# beer_machine_HAT.net
KiCad netlist of a schematic drawn in EAGLE
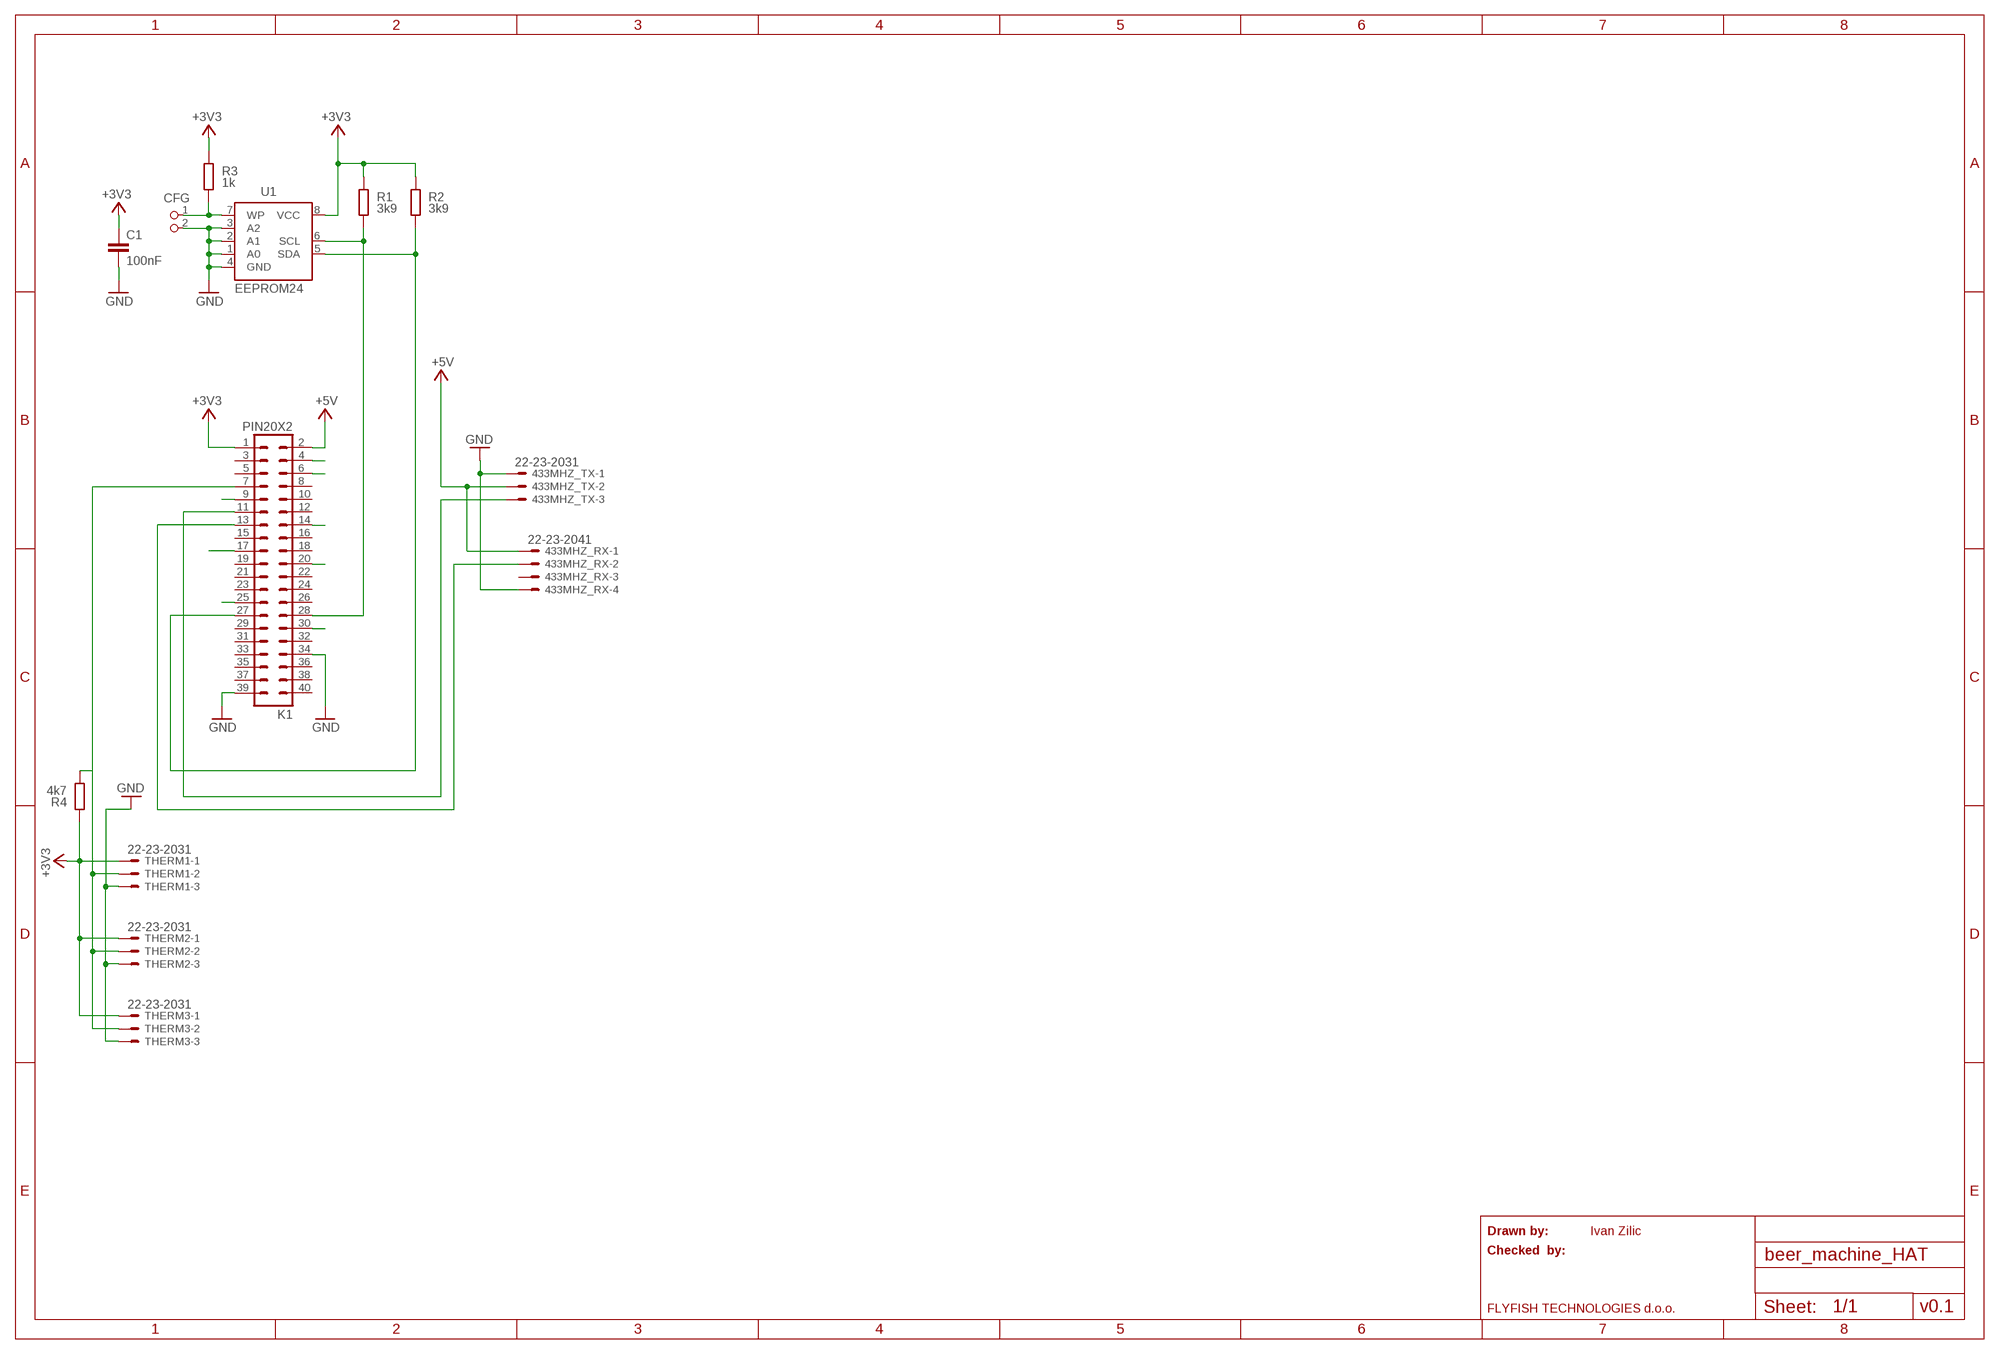
[diagram p0: schematic, sheet 1]

(export (version "E")
  (design (tool "Eeschema 10.0.6"))
  (components
    (comp (ref "433MHZ_RX")
      (value "22-23-2041")
      (footprint "eagle-import:22-23-2041")
      (fields (field (name "MF") "MOLEX"))
      (libsource (lib "eagle-import") (part "22-23-2041"))
    )
    (comp (ref "433MHZ_TX")
      (value "22-23-2031")
      (footprint "eagle-import:22-23-2031")
      (fields (field (name "MF") "MOLEX"))
      (libsource (lib "eagle-import") (part "22-23-2031"))
    )
    (comp (ref "C1")
      (value "100nF")
      (footprint "eagle-import:C0805K")
      (libsource (lib "eagle-import") (part "C-EUC0805K"))
    )
    (comp (ref "CFG")
      (value "PIN2_100")
      (footprint "eagle-import:PIN_W_2")
      (libsource (lib "eagle-import") (part "PIN2_100"))
    )
    (comp (ref "K1")
      (value "PIN20X2")
      (footprint "eagle-import:PIN_20X2")
      (libsource (lib "eagle-import") (part "PIN20X2"))
    )
    (comp (ref "R1")
      (value "3k9")
      (footprint "eagle-import:M0805")
      (fields (field (name "TOLERANCE") "5%"))
      (libsource (lib "eagle-import") (part "R-EU_M0805"))
    )
    (comp (ref "R2")
      (value "3k9")
      (footprint "eagle-import:M0805")
      (fields (field (name "TOLERANCE") "5%"))
      (libsource (lib "eagle-import") (part "R-EU_M0805"))
    )
    (comp (ref "R3")
      (value "1k")
      (footprint "eagle-import:M0805")
      (fields (field (name "TOLERANCE") "5%"))
      (libsource (lib "eagle-import") (part "R-EU_M0805"))
    )
    (comp (ref "R4")
      (value "4k7")
      (footprint "eagle-import:M0805")
      (fields (field (name "TOLERANCE") "5%"))
      (libsource (lib "eagle-import") (part "R-EU_M0805"))
    )
    (comp (ref "THERM1")
      (value "22-23-2031")
      (footprint "eagle-import:22-23-2031")
      (fields (field (name "MF") "MOLEX"))
      (libsource (lib "eagle-import") (part "22-23-2031"))
    )
    (comp (ref "THERM2")
      (value "22-23-2031")
      (footprint "eagle-import:22-23-2031")
      (fields (field (name "MF") "MOLEX"))
      (libsource (lib "eagle-import") (part "22-23-2031"))
    )
    (comp (ref "THERM3")
      (value "22-23-2031")
      (footprint "eagle-import:22-23-2031")
      (fields (field (name "MF") "MOLEX"))
      (libsource (lib "eagle-import") (part "22-23-2031"))
    )
    (comp (ref "U1")
      (value "EEPROM24")
      (footprint "eagle-import:SOIC8")
      (libsource (lib "eagle-import") (part "EEPROM24"))
    )
  )
  (nets
    (net (code "1") (name "+3V3") (class "Default")
      (node (ref "C1") (pin "1") (pinfunction "1_1") (pintype "passive"))
      (node (ref "K1") (pin "1") (pinfunction "1_1") (pintype "passive"))
      (node (ref "R1") (pin "2") (pinfunction "2_2") (pintype "passive"))
      (node (ref "R2") (pin "2") (pinfunction "2_2") (pintype "passive"))
      (node (ref "R3") (pin "2") (pinfunction "2_2") (pintype "passive"))
      (node (ref "R4") (pin "2") (pinfunction "2_2") (pintype "passive"))
      (node (ref "THERM1") (pin "1") (pinfunction "S_1") (pintype "passive"))
      (node (ref "THERM2") (pin "1") (pinfunction "S_1") (pintype "passive"))
      (node (ref "THERM3") (pin "1") (pinfunction "S_1") (pintype "passive"))
      (node (ref "U1") (pin "8") (pinfunction "VCC_8") (pintype "power_in"))
    )
    (net (code "2") (name "+5V") (class "Default")
      (node (ref "433MHZ_RX") (pin "1") (pinfunction "S_1") (pintype "passive"))
      (node (ref "433MHZ_TX") (pin "2") (pinfunction "S_2") (pintype "passive"))
      (node (ref "K1") (pin "2") (pinfunction "2_2") (pintype "passive"))
    )
    (net (code "3") (name "GND") (class "Default")
      (node (ref "433MHZ_RX") (pin "4") (pinfunction "S_4") (pintype "passive"))
      (node (ref "433MHZ_TX") (pin "1") (pinfunction "S_1") (pintype "passive"))
      (node (ref "C1") (pin "2") (pinfunction "2_2") (pintype "passive"))
      (node (ref "CFG") (pin "2") (pinfunction "2_2") (pintype "passive"))
      (node (ref "K1") (pin "34") (pinfunction "34_34") (pintype "passive"))
      (node (ref "K1") (pin "39") (pinfunction "39_39") (pintype "passive"))
      (node (ref "THERM1") (pin "3") (pinfunction "S_3") (pintype "passive"))
      (node (ref "THERM2") (pin "3") (pinfunction "S_3") (pintype "passive"))
      (node (ref "THERM3") (pin "3") (pinfunction "S_3") (pintype "passive"))
      (node (ref "U1") (pin "1") (pinfunction "A0_1") (pintype "input"))
      (node (ref "U1") (pin "2") (pinfunction "A1_2") (pintype "input"))
      (node (ref "U1") (pin "3") (pinfunction "A2_3") (pintype "input"))
      (node (ref "U1") (pin "4") (pinfunction "GND_4") (pintype "power_in"))
    )
    (net (code "4") (name "Net-(433MHZ_RXB-S)") (class "Default")
      (node (ref "433MHZ_RX") (pin "2") (pinfunction "S_2") (pintype "passive"))
      (node (ref "K1") (pin "13") (pinfunction "13_13") (pintype "passive"))
    )
    (net (code "5") (name "Net-(433MHZ_TXC-S)") (class "Default")
      (node (ref "433MHZ_TX") (pin "3") (pinfunction "S_3") (pintype "passive"))
      (node (ref "K1") (pin "11") (pinfunction "11_11") (pintype "passive"))
    )
    (net (code "6") (name "Net-(THERM1B-S)") (class "Default")
      (node (ref "K1") (pin "7") (pinfunction "7_7") (pintype "passive"))
      (node (ref "R4") (pin "1") (pinfunction "1_1") (pintype "passive"))
      (node (ref "THERM1") (pin "2") (pinfunction "S_2") (pintype "passive"))
      (node (ref "THERM2") (pin "2") (pinfunction "S_2") (pintype "passive"))
      (node (ref "THERM3") (pin "2") (pinfunction "S_2") (pintype "passive"))
    )
    (net (code "7") (name "Net-(U1-SCL)") (class "Default")
      (node (ref "K1") (pin "28") (pinfunction "28_28") (pintype "passive"))
      (node (ref "R1") (pin "1") (pinfunction "1_1") (pintype "passive"))
      (node (ref "U1") (pin "6") (pinfunction "SCL_6") (pintype "input"))
    )
    (net (code "8") (name "Net-(U1-SDA)") (class "Default")
      (node (ref "K1") (pin "27") (pinfunction "27_27") (pintype "passive"))
      (node (ref "R2") (pin "1") (pinfunction "1_1") (pintype "passive"))
      (node (ref "U1") (pin "5") (pinfunction "SDA_5") (pintype "bidirectional"))
    )
    (net (code "9") (name "Net-(U1-WP)") (class "Default")
      (node (ref "CFG") (pin "1") (pinfunction "1_1") (pintype "passive"))
      (node (ref "R3") (pin "1") (pinfunction "1_1") (pintype "passive"))
      (node (ref "U1") (pin "7") (pinfunction "WP_7") (pintype "input"))
    )
    (net (code "10") (name "unconnected-(433MHZ_RXC-S-Pad3)") (class "Default")
      (node (ref "433MHZ_RX") (pin "3") (pinfunction "S_3") (pintype "passive"))
    )
    (net (code "11") (name "unconnected-(K1-Pad3)") (class "Default")
      (node (ref "K1") (pin "3") (pinfunction "3_3") (pintype "passive"))
    )
    (net (code "12") (name "unconnected-(K1-Pad4)") (class "Default")
      (node (ref "K1") (pin "4") (pinfunction "4_4") (pintype "passive"))
    )
    (net (code "13") (name "unconnected-(K1-Pad5)") (class "Default")
      (node (ref "K1") (pin "5") (pinfunction "5_5") (pintype "passive"))
    )
    (net (code "14") (name "unconnected-(K1-Pad6)") (class "Default")
      (node (ref "K1") (pin "6") (pinfunction "6_6") (pintype "passive"))
    )
    (net (code "15") (name "unconnected-(K1-Pad8)") (class "Default")
      (node (ref "K1") (pin "8") (pinfunction "8_8") (pintype "passive"))
    )
    (net (code "16") (name "unconnected-(K1-Pad9)") (class "Default")
      (node (ref "K1") (pin "9") (pinfunction "9_9") (pintype "passive"))
    )
    (net (code "17") (name "unconnected-(K1-Pad10)") (class "Default")
      (node (ref "K1") (pin "10") (pinfunction "10_10") (pintype "passive"))
    )
    (net (code "18") (name "unconnected-(K1-Pad12)") (class "Default")
      (node (ref "K1") (pin "12") (pinfunction "12_12") (pintype "passive"))
    )
    (net (code "19") (name "unconnected-(K1-Pad14)") (class "Default")
      (node (ref "K1") (pin "14") (pinfunction "14_14") (pintype "passive"))
    )
    (net (code "20") (name "unconnected-(K1-Pad15)") (class "Default")
      (node (ref "K1") (pin "15") (pinfunction "15_15") (pintype "passive"))
    )
    (net (code "21") (name "unconnected-(K1-Pad16)") (class "Default")
      (node (ref "K1") (pin "16") (pinfunction "16_16") (pintype "passive"))
    )
    (net (code "22") (name "unconnected-(K1-Pad17)") (class "Default")
      (node (ref "K1") (pin "17") (pinfunction "17_17") (pintype "passive"))
    )
    (net (code "23") (name "unconnected-(K1-Pad18)") (class "Default")
      (node (ref "K1") (pin "18") (pinfunction "18_18") (pintype "passive"))
    )
    (net (code "24") (name "unconnected-(K1-Pad19)") (class "Default")
      (node (ref "K1") (pin "19") (pinfunction "19_19") (pintype "passive"))
    )
    (net (code "25") (name "unconnected-(K1-Pad20)") (class "Default")
      (node (ref "K1") (pin "20") (pinfunction "20_20") (pintype "passive"))
    )
    (net (code "26") (name "unconnected-(K1-Pad21)") (class "Default")
      (node (ref "K1") (pin "21") (pinfunction "21_21") (pintype "passive"))
    )
    (net (code "27") (name "unconnected-(K1-Pad22)") (class "Default")
      (node (ref "K1") (pin "22") (pinfunction "22_22") (pintype "passive"))
    )
    (net (code "28") (name "unconnected-(K1-Pad23)") (class "Default")
      (node (ref "K1") (pin "23") (pinfunction "23_23") (pintype "passive"))
    )
    (net (code "29") (name "unconnected-(K1-Pad24)") (class "Default")
      (node (ref "K1") (pin "24") (pinfunction "24_24") (pintype "passive"))
    )
    (net (code "30") (name "unconnected-(K1-Pad25)") (class "Default")
      (node (ref "K1") (pin "25") (pinfunction "25_25") (pintype "passive"))
    )
    (net (code "31") (name "unconnected-(K1-Pad26)") (class "Default")
      (node (ref "K1") (pin "26") (pinfunction "26_26") (pintype "passive"))
    )
    (net (code "32") (name "unconnected-(K1-Pad29)") (class "Default")
      (node (ref "K1") (pin "29") (pinfunction "29_29") (pintype "passive"))
    )
    (net (code "33") (name "unconnected-(K1-Pad30)") (class "Default")
      (node (ref "K1") (pin "30") (pinfunction "30_30") (pintype "passive"))
    )
    (net (code "34") (name "unconnected-(K1-Pad31)") (class "Default")
      (node (ref "K1") (pin "31") (pinfunction "31_31") (pintype "passive"))
    )
    (net (code "35") (name "unconnected-(K1-Pad32)") (class "Default")
      (node (ref "K1") (pin "32") (pinfunction "32_32") (pintype "passive"))
    )
    (net (code "36") (name "unconnected-(K1-Pad33)") (class "Default")
      (node (ref "K1") (pin "33") (pinfunction "33_33") (pintype "passive"))
    )
    (net (code "37") (name "unconnected-(K1-Pad35)") (class "Default")
      (node (ref "K1") (pin "35") (pinfunction "35_35") (pintype "passive"))
    )
    (net (code "38") (name "unconnected-(K1-Pad36)") (class "Default")
      (node (ref "K1") (pin "36") (pinfunction "36_36") (pintype "passive"))
    )
    (net (code "39") (name "unconnected-(K1-Pad37)") (class "Default")
      (node (ref "K1") (pin "37") (pinfunction "37_37") (pintype "passive"))
    )
    (net (code "40") (name "unconnected-(K1-Pad38)") (class "Default")
      (node (ref "K1") (pin "38") (pinfunction "38_38") (pintype "passive"))
    )
    (net (code "41") (name "unconnected-(K1-Pad40)") (class "Default")
      (node (ref "K1") (pin "40") (pinfunction "40_40") (pintype "passive"))
    )
  )
)
